# envelope_detector.net
KiCad netlist of a schematic drawn in EAGLE
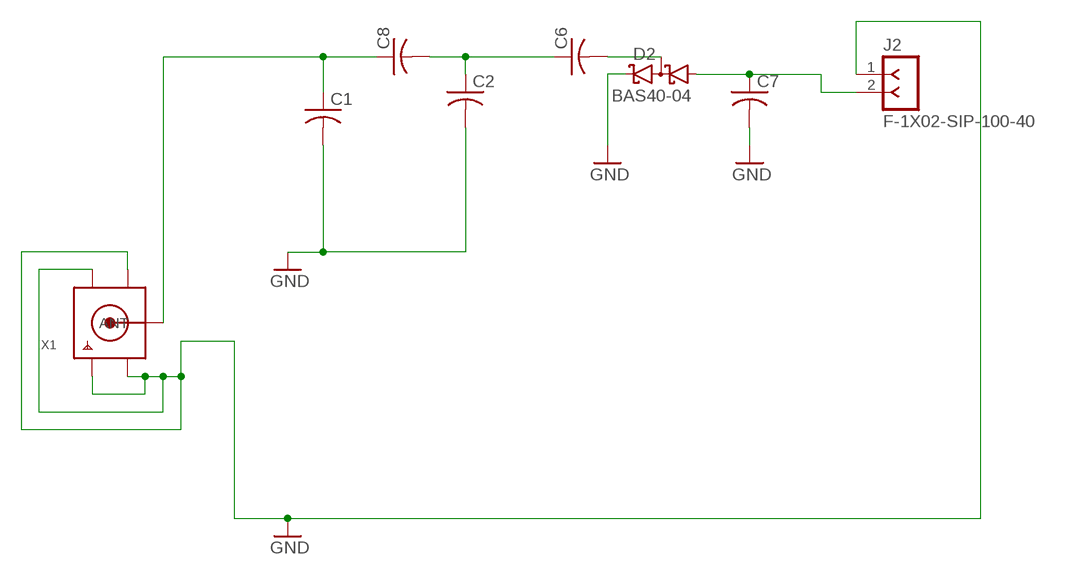
[diagram p0: schematic, sheet 1]

(export (version "E")
  (design (tool "Eeschema 10.0.6"))
  (components
    (comp (ref "C1")
      (value "C-USC0805")
      (footprint "eagle-import:C0805")
      (libsource (lib "eagle-import") (part "C-USC0805"))
    )
    (comp (ref "C2")
      (value "C-USC0805")
      (footprint "eagle-import:C0805")
      (libsource (lib "eagle-import") (part "C-USC0805"))
    )
    (comp (ref "C6")
      (value "C-USC0805")
      (footprint "eagle-import:C0805")
      (libsource (lib "eagle-import") (part "C-USC0805"))
    )
    (comp (ref "C7")
      (value "C-USC0805")
      (footprint "eagle-import:C0805")
      (libsource (lib "eagle-import") (part "C-USC0805"))
    )
    (comp (ref "C8")
      (value "C-USC0805")
      (footprint "eagle-import:C0805")
      (libsource (lib "eagle-import") (part "C-USC0805"))
    )
    (comp (ref "D2")
      (value "BAS40-04")
      (footprint "eagle-import:SOT23")
      (libsource (lib "eagle-import") (part "BAS40-04"))
    )
    (comp (ref "J2")
      (value "F-1X02-SIP-100-40")
      (footprint "eagle-import:SIP-100-02-40")
      (libsource (lib "eagle-import") (part "F-1X02-SIP-100-40"))
    )
    (comp (ref "X1")
      (value "SMACONNECTOR_EDGE")
      (footprint "eagle-import:SMA_EDGELAUNCH")
      (libsource (lib "eagle-import") (part "SMACONNECTOR_EDGE"))
    )
  )
  (nets
    (net (code "1") (name "GND") (class "Default")
      (node (ref "C1") (pin "2") (pinfunction "2_2") (pintype "passive"))
      (node (ref "C2") (pin "2") (pinfunction "2_2") (pintype "passive"))
      (node (ref "C7") (pin "2") (pinfunction "2_2") (pintype "passive"))
      (node (ref "D2") (pin "2") (pinfunction "C2_2") (pintype "passive"))
      (node (ref "J2") (pin "1") (pinfunction "1_1") (pintype "passive"))
      (node (ref "X1") (pin "GND@1") (pinfunction "GND4_GND@1") (pintype "power_in"))
      (node (ref "X1") (pin "GND@2") (pinfunction "GND3_GND@2") (pintype "power_in"))
      (node (ref "X1") (pin "GND@3") (pinfunction "GND2_GND@3") (pintype "power_in"))
      (node (ref "X1") (pin "GND@4") (pinfunction "GND1_GND@4") (pintype "power_in"))
    )
    (net (code "2") (name "Net-(C2-Pad1)") (class "Default")
      (node (ref "C2") (pin "1") (pinfunction "1_1") (pintype "passive"))
      (node (ref "C6") (pin "1") (pinfunction "1_1") (pintype "passive"))
      (node (ref "C8") (pin "2") (pinfunction "2_2") (pintype "passive"))
    )
    (net (code "3") (name "Net-(D2-A1)") (class "Default")
      (node (ref "C7") (pin "1") (pinfunction "1_1") (pintype "passive"))
      (node (ref "D2") (pin "1") (pinfunction "A1_1") (pintype "passive"))
      (node (ref "J2") (pin "2") (pinfunction "2_2") (pintype "passive"))
    )
    (net (code "4") (name "Net-(D2-C1A2)") (class "Default")
      (node (ref "C6") (pin "2") (pinfunction "2_2") (pintype "passive"))
      (node (ref "D2") (pin "3") (pinfunction "C1A2_3") (pintype "passive"))
    )
    (net (code "5") (name "Net-(X1-ANT)") (class "Default")
      (node (ref "C1") (pin "1") (pinfunction "1_1") (pintype "passive"))
      (node (ref "C8") (pin "1") (pinfunction "1_1") (pintype "passive"))
      (node (ref "X1") (pin "P") (pinfunction "ANT_P") (pintype "bidirectional"))
    )
  )
)
